# Cizgi_Sensoru.net
KiCad netlist of a schematic drawn in EAGLE
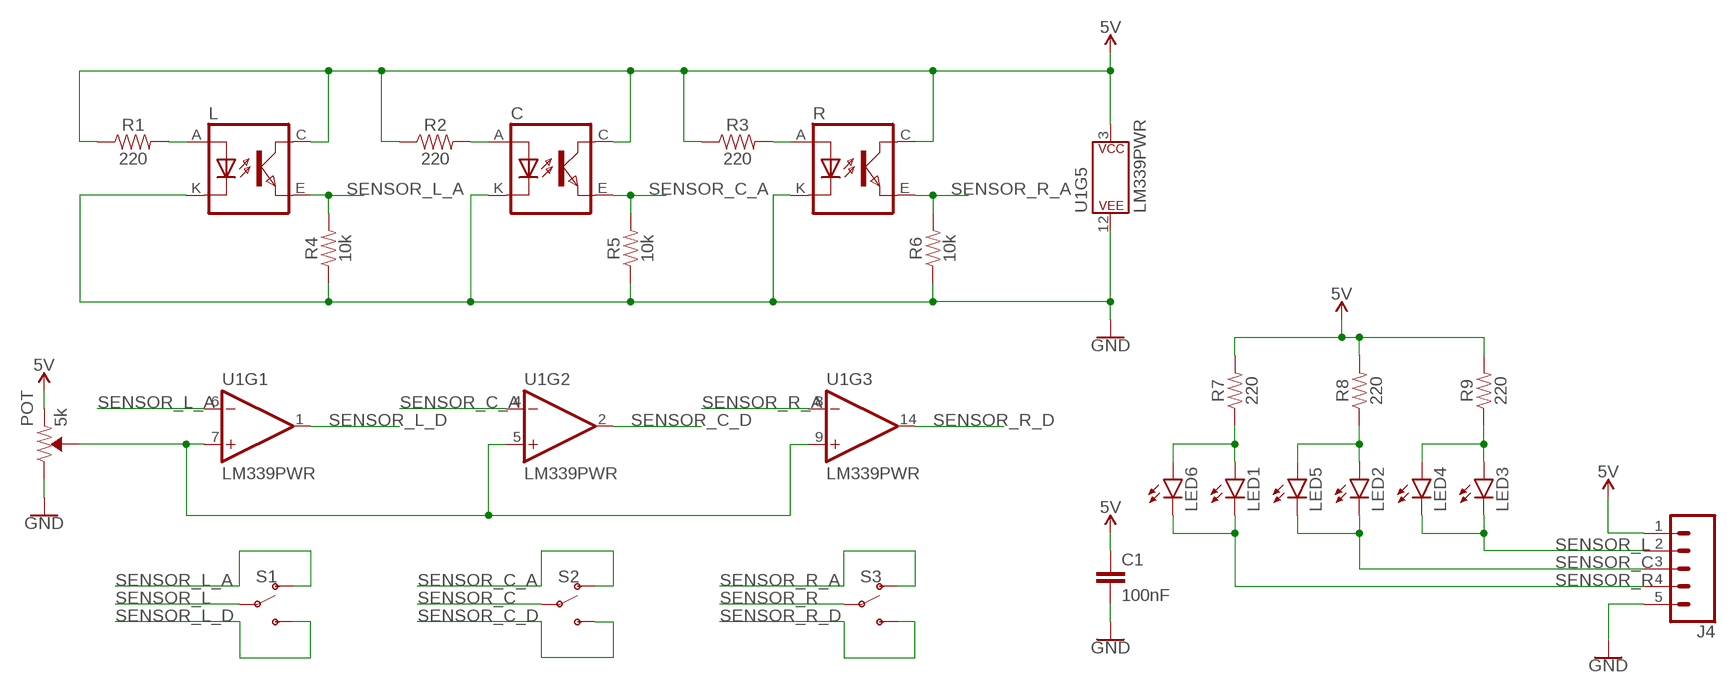
[diagram p0: schematic, sheet 1]

(export (version "E")
  (design (tool "Eeschema 10.0.6"))
  (components
    (comp (ref "C")
      (value "TCRT5000")
      (footprint "eagle-import:TCRT5000")
      (libsource (lib "eagle-import") (part "TCRT5000"))
    )
    (comp (ref "C1")
      (value "100nF")
      (footprint "eagle-import:0805")
      (libsource (lib "eagle-import") (part "0.33UF/330NF-0805-50V-10%"))
    )
    (comp (ref "J4")
      (value "CONN_05")
      (footprint "eagle-import:1X05")
      (libsource (lib "eagle-import") (part "CONN_05"))
    )
    (comp (ref "L")
      (value "TCRT5000")
      (footprint "eagle-import:TCRT5000")
      (libsource (lib "eagle-import") (part "TCRT5000"))
    )
    (comp (ref "LED1")
      (value "LEDSML0805")
      (footprint "eagle-import:SML0805")
      (libsource (lib "eagle-import") (part "LEDSML0805"))
    )
    (comp (ref "LED2")
      (value "LEDSML0805")
      (footprint "eagle-import:SML0805")
      (libsource (lib "eagle-import") (part "LEDSML0805"))
    )
    (comp (ref "LED3")
      (value "LEDSML0805")
      (footprint "eagle-import:SML0805")
      (libsource (lib "eagle-import") (part "LEDSML0805"))
    )
    (comp (ref "LED4")
      (value "LEDSML0805")
      (footprint "eagle-import:SML0805")
      (libsource (lib "eagle-import") (part "LEDSML0805"))
    )
    (comp (ref "LED5")
      (value "LEDSML0805")
      (footprint "eagle-import:SML0805")
      (libsource (lib "eagle-import") (part "LEDSML0805"))
    )
    (comp (ref "LED6")
      (value "LEDSML0805")
      (footprint "eagle-import:SML0805")
      (libsource (lib "eagle-import") (part "LEDSML0805"))
    )
    (comp (ref "POT")
      (value "5k")
      (footprint "eagle-import:TRIMPOT-SMD-5MM")
      (libsource (lib "eagle-import") (part "TRIMPOT-SMD-5MM-CLOSED-1/4W-20%"))
    )
    (comp (ref "R")
      (value "TCRT5000")
      (footprint "eagle-import:TCRT5000")
      (libsource (lib "eagle-import") (part "TCRT5000"))
    )
    (comp (ref "R1")
      (value "220")
      (footprint "eagle-import:0805")
      (libsource (lib "eagle-import") (part "0.22OHM-0805-1/4W-1%"))
    )
    (comp (ref "R2")
      (value "220")
      (footprint "eagle-import:0805")
      (libsource (lib "eagle-import") (part "0.22OHM-0805-1/4W-1%"))
    )
    (comp (ref "R3")
      (value "220")
      (footprint "eagle-import:0805")
      (libsource (lib "eagle-import") (part "0.22OHM-0805-1/4W-1%"))
    )
    (comp (ref "R4")
      (value "10k")
      (footprint "eagle-import:0805")
      (libsource (lib "eagle-import") (part "0.22OHM-0805-1/4W-1%"))
    )
    (comp (ref "R5")
      (value "10k")
      (footprint "eagle-import:0805")
      (libsource (lib "eagle-import") (part "0.22OHM-0805-1/4W-1%"))
    )
    (comp (ref "R6")
      (value "10k")
      (footprint "eagle-import:0805")
      (libsource (lib "eagle-import") (part "0.22OHM-0805-1/4W-1%"))
    )
    (comp (ref "R7")
      (value "220")
      (footprint "eagle-import:0805")
      (libsource (lib "eagle-import") (part "0.22OHM-0805-1/4W-1%"))
    )
    (comp (ref "R8")
      (value "220")
      (footprint "eagle-import:0805")
      (libsource (lib "eagle-import") (part "0.22OHM-0805-1/4W-1%"))
    )
    (comp (ref "R9")
      (value "220")
      (footprint "eagle-import:0805")
      (libsource (lib "eagle-import") (part "0.22OHM-0805-1/4W-1%"))
    )
    (comp (ref "S1")
      (value "SWITCH-SPDT-SMD-RIGHT-ANGLE")
      (footprint "eagle-import:SWITCH_SPST_SMD_A")
      (libsource (lib "eagle-import") (part "SWITCH-SPDT-SMD-RIGHT-ANGLE"))
    )
    (comp (ref "S2")
      (value "SWITCH-SPDT-SMD-RIGHT-ANGLE")
      (footprint "eagle-import:SWITCH_SPST_SMD_A")
      (libsource (lib "eagle-import") (part "SWITCH-SPDT-SMD-RIGHT-ANGLE"))
    )
    (comp (ref "S3")
      (value "SWITCH-SPDT-SMD-RIGHT-ANGLE")
      (footprint "eagle-import:SWITCH_SPST_SMD_A")
      (libsource (lib "eagle-import") (part "SWITCH-SPDT-SMD-RIGHT-ANGLE"))
    )
    (comp (ref "U1")
      (value "LM339PWR")
      (footprint "eagle-import:TSSOP-14")
      (libsource (lib "eagle-import") (part "LM339"))
    )
  )
  (nets
    (net (code "1") (name "/SENSOR_C") (class "Default")
      (node (ref "J4") (pin "3") (pinfunction "3_3") (pintype "passive"))
      (node (ref "LED2") (pin "C") (pinfunction "C_C") (pintype "passive"))
      (node (ref "LED5") (pin "C") (pinfunction "C_C") (pintype "passive"))
      (node (ref "S2") (pin "2") (pinfunction "P_2") (pintype "passive"))
    )
    (net (code "2") (name "/SENSOR_C_A") (class "Default")
      (node (ref "C") (pin "E") (pinfunction "EMITTER_E") (pintype "passive"))
      (node (ref "R5") (pin "2") (pinfunction "2_2") (pintype "passive"))
      (node (ref "S2") (pin "1") (pinfunction "O_1") (pintype "passive"))
      (node (ref "U1") (pin "4") (pinfunction "-IN_4") (pintype "input"))
    )
    (net (code "3") (name "/SENSOR_C_D") (class "Default")
      (node (ref "S2") (pin "3") (pinfunction "S_3") (pintype "passive"))
      (node (ref "U1") (pin "2") (pinfunction "OUT_2") (pintype "output"))
    )
    (net (code "4") (name "/SENSOR_L") (class "Default")
      (node (ref "J4") (pin "2") (pinfunction "2_2") (pintype "passive"))
      (node (ref "LED3") (pin "C") (pinfunction "C_C") (pintype "passive"))
      (node (ref "LED4") (pin "C") (pinfunction "C_C") (pintype "passive"))
      (node (ref "S1") (pin "2") (pinfunction "P_2") (pintype "passive"))
    )
    (net (code "5") (name "/SENSOR_L_A") (class "Default")
      (node (ref "L") (pin "E") (pinfunction "EMITTER_E") (pintype "passive"))
      (node (ref "R4") (pin "2") (pinfunction "2_2") (pintype "passive"))
      (node (ref "S1") (pin "1") (pinfunction "O_1") (pintype "passive"))
      (node (ref "U1") (pin "6") (pinfunction "-IN_6") (pintype "input"))
    )
    (net (code "6") (name "/SENSOR_L_D") (class "Default")
      (node (ref "S1") (pin "3") (pinfunction "S_3") (pintype "passive"))
      (node (ref "U1") (pin "1") (pinfunction "OUT_1") (pintype "output"))
    )
    (net (code "7") (name "/SENSOR_R") (class "Default")
      (node (ref "J4") (pin "4") (pinfunction "4_4") (pintype "passive"))
      (node (ref "LED1") (pin "C") (pinfunction "C_C") (pintype "passive"))
      (node (ref "LED6") (pin "C") (pinfunction "C_C") (pintype "passive"))
      (node (ref "S3") (pin "2") (pinfunction "P_2") (pintype "passive"))
    )
    (net (code "8") (name "/SENSOR_R_A") (class "Default")
      (node (ref "R") (pin "E") (pinfunction "EMITTER_E") (pintype "passive"))
      (node (ref "R6") (pin "2") (pinfunction "2_2") (pintype "passive"))
      (node (ref "S3") (pin "1") (pinfunction "O_1") (pintype "passive"))
      (node (ref "U1") (pin "8") (pinfunction "-IN_8") (pintype "input"))
    )
    (net (code "9") (name "/SENSOR_R_D") (class "Default")
      (node (ref "S3") (pin "3") (pinfunction "S_3") (pintype "passive"))
      (node (ref "U1") (pin "14") (pinfunction "OUT_14") (pintype "output"))
    )
    (net (code "10") (name "5V") (class "Default")
      (node (ref "C") (pin "C") (pinfunction "COLLECTOR_C") (pintype "passive"))
      (node (ref "C1") (pin "1") (pinfunction "1_1") (pintype "passive"))
      (node (ref "J4") (pin "1") (pinfunction "1_1") (pintype "passive"))
      (node (ref "L") (pin "C") (pinfunction "COLLECTOR_C") (pintype "passive"))
      (node (ref "POT") (pin "A") (pinfunction "CCW_A") (pintype "passive"))
      (node (ref "R") (pin "C") (pinfunction "COLLECTOR_C") (pintype "passive"))
      (node (ref "R1") (pin "1") (pinfunction "1_1") (pintype "passive"))
      (node (ref "R2") (pin "1") (pinfunction "1_1") (pintype "passive"))
      (node (ref "R3") (pin "1") (pinfunction "1_1") (pintype "passive"))
      (node (ref "R7") (pin "2") (pinfunction "2_2") (pintype "passive"))
      (node (ref "R8") (pin "2") (pinfunction "2_2") (pintype "passive"))
      (node (ref "R9") (pin "2") (pinfunction "2_2") (pintype "passive"))
      (node (ref "U1") (pin "3") (pinfunction "P$V+_3") (pintype "bidirectional"))
    )
    (net (code "11") (name "GND") (class "Default")
      (node (ref "C") (pin "K") (pinfunction "CATHODE_K") (pintype "passive"))
      (node (ref "C1") (pin "2") (pinfunction "2_2") (pintype "passive"))
      (node (ref "J4") (pin "5") (pinfunction "5_5") (pintype "passive"))
      (node (ref "L") (pin "K") (pinfunction "CATHODE_K") (pintype "passive"))
      (node (ref "POT") (pin "C") (pinfunction "CW_C") (pintype "passive"))
      (node (ref "R") (pin "K") (pinfunction "CATHODE_K") (pintype "passive"))
      (node (ref "R4") (pin "1") (pinfunction "1_1") (pintype "passive"))
      (node (ref "R5") (pin "1") (pinfunction "1_1") (pintype "passive"))
      (node (ref "R6") (pin "1") (pinfunction "1_1") (pintype "passive"))
      (node (ref "U1") (pin "12") (pinfunction "P$V-_12") (pintype "bidirectional"))
    )
    (net (code "12") (name "Net-(C-ANODE)") (class "Default")
      (node (ref "C") (pin "A") (pinfunction "ANODE_A") (pintype "passive"))
      (node (ref "R2") (pin "2") (pinfunction "2_2") (pintype "passive"))
    )
    (net (code "13") (name "Net-(L-ANODE)") (class "Default")
      (node (ref "L") (pin "A") (pinfunction "ANODE_A") (pintype "passive"))
      (node (ref "R1") (pin "2") (pinfunction "2_2") (pintype "passive"))
    )
    (net (code "14") (name "Net-(LED1-PadA)") (class "Default")
      (node (ref "LED1") (pin "A") (pinfunction "A_A") (pintype "passive"))
      (node (ref "LED6") (pin "A") (pinfunction "A_A") (pintype "passive"))
      (node (ref "R7") (pin "1") (pinfunction "1_1") (pintype "passive"))
    )
    (net (code "15") (name "Net-(LED2-PadA)") (class "Default")
      (node (ref "LED2") (pin "A") (pinfunction "A_A") (pintype "passive"))
      (node (ref "LED5") (pin "A") (pinfunction "A_A") (pintype "passive"))
      (node (ref "R8") (pin "1") (pinfunction "1_1") (pintype "passive"))
    )
    (net (code "16") (name "Net-(LED3-PadA)") (class "Default")
      (node (ref "LED3") (pin "A") (pinfunction "A_A") (pintype "passive"))
      (node (ref "LED4") (pin "A") (pinfunction "A_A") (pintype "passive"))
      (node (ref "R9") (pin "1") (pinfunction "1_1") (pintype "passive"))
    )
    (net (code "17") (name "Net-(POT-WIPER)") (class "Default")
      (node (ref "POT") (pin "B") (pinfunction "WIPER_B") (pintype "passive"))
      (node (ref "U1") (pin "5") (pinfunction "+IN_5") (pintype "input"))
      (node (ref "U1") (pin "7") (pinfunction "+IN_7") (pintype "input"))
      (node (ref "U1") (pin "9") (pinfunction "+IN_9") (pintype "input"))
    )
    (net (code "18") (name "Net-(R-ANODE)") (class "Default")
      (node (ref "R") (pin "A") (pinfunction "ANODE_A") (pintype "passive"))
      (node (ref "R3") (pin "2") (pinfunction "2_2") (pintype "passive"))
    )
  )
)
